# POWER_reset.net
KiCad netlist of a schematic drawn in EAGLE
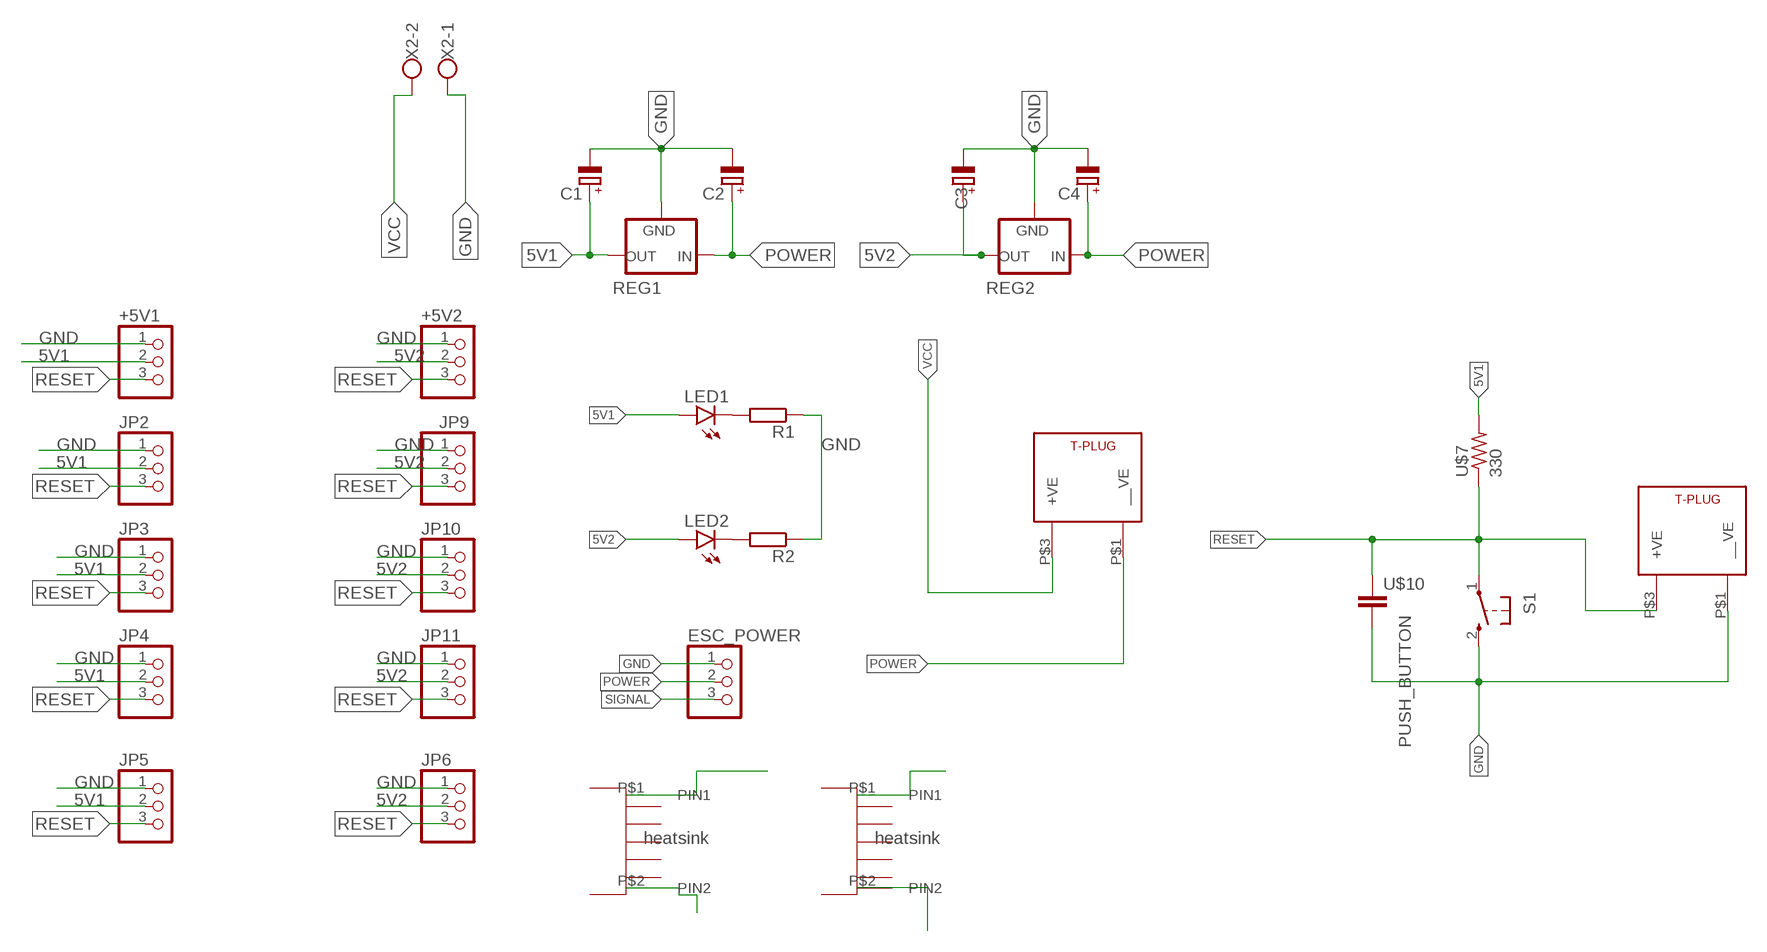
[diagram p0: schematic, sheet 1]

(export (version "E")
  (design (tool "Eeschema 10.0.6"))
  (components
    (comp (ref "+5V1")
      (value "PINHD-3_DATA")
      (footprint "eagle-import:1X03_DATA")
      (libsource (lib "eagle-import") (part "PINHD-3_DATA"))
    )
    (comp (ref "+5V2")
      (value "PINHD-3_DATA")
      (footprint "eagle-import:1X03_DATA")
      (libsource (lib "eagle-import") (part "PINHD-3_DATA"))
    )
    (comp (ref "C1")
      (value "CAP_POL")
      (footprint "eagle-import:E3,5-8")
      (libsource (lib "eagle-import") (part "CAP_POL"))
    )
    (comp (ref "C2")
      (value "CAP_POL")
      (footprint "eagle-import:E3,5-8")
      (libsource (lib "eagle-import") (part "CAP_POL"))
    )
    (comp (ref "C3")
      (value "CAP_POL")
      (footprint "eagle-import:E3,5-8")
      (libsource (lib "eagle-import") (part "CAP_POL"))
    )
    (comp (ref "C4")
      (value "CAP_POL")
      (footprint "eagle-import:E3,5-8")
      (libsource (lib "eagle-import") (part "CAP_POL"))
    )
    (comp (ref "ESC_POWER")
      (value "PINHD-3_DATA")
      (footprint "eagle-import:1X03_DATA")
      (libsource (lib "eagle-import") (part "PINHD-3_DATA"))
    )
    (comp (ref "JP2")
      (value "PINHD-3_DATA")
      (footprint "eagle-import:1X03_DATA")
      (libsource (lib "eagle-import") (part "PINHD-3_DATA"))
    )
    (comp (ref "JP3")
      (value "PINHD-3_DATA")
      (footprint "eagle-import:1X03_DATA")
      (libsource (lib "eagle-import") (part "PINHD-3_DATA"))
    )
    (comp (ref "JP4")
      (value "PINHD-3_DATA")
      (footprint "eagle-import:1X03_DATA")
      (libsource (lib "eagle-import") (part "PINHD-3_DATA"))
    )
    (comp (ref "JP5")
      (value "PINHD-3_DATA")
      (footprint "eagle-import:1X03_DATA")
      (libsource (lib "eagle-import") (part "PINHD-3_DATA"))
    )
    (comp (ref "JP6")
      (value "PINHD-3_DATA")
      (footprint "eagle-import:1X03_DATA")
      (libsource (lib "eagle-import") (part "PINHD-3_DATA"))
    )
    (comp (ref "JP9")
      (value "PINHD-3_DATA")
      (footprint "eagle-import:1X03_DATA")
      (libsource (lib "eagle-import") (part "PINHD-3_DATA"))
    )
    (comp (ref "JP10")
      (value "PINHD-3_DATA")
      (footprint "eagle-import:1X03_DATA")
      (libsource (lib "eagle-import") (part "PINHD-3_DATA"))
    )
    (comp (ref "JP11")
      (value "PINHD-3_DATA")
      (footprint "eagle-import:1X03_DATA")
      (libsource (lib "eagle-import") (part "PINHD-3_DATA"))
    )
    (comp (ref "LED1")
      (value "LED5MM")
      (footprint "eagle-import:LED5MM")
      (libsource (lib "eagle-import") (part "LED5MM"))
    )
    (comp (ref "LED2")
      (value "LED5MM")
      (footprint "eagle-import:LED5MM")
      (libsource (lib "eagle-import") (part "LED5MM"))
    )
    (comp (ref "R1")
      (value "R-EU_0204/7")
      (footprint "eagle-import:0204_7")
      (libsource (lib "eagle-import") (part "R-EU_0204/7"))
    )
    (comp (ref "R2")
      (value "R-EU_0204/7")
      (footprint "eagle-import:0204_7")
      (libsource (lib "eagle-import") (part "R-EU_0204/7"))
    )
    (comp (ref "REG1")
      (value "78XXS")
      (footprint "eagle-import:78XXS")
      (libsource (lib "eagle-import") (part "78XXS"))
    )
    (comp (ref "REG2")
      (value "78XXS")
      (footprint "eagle-import:78XXS")
      (libsource (lib "eagle-import") (part "78XXS"))
    )
    (comp (ref "S1")
      (value "PUSH_BUTTON")
      (footprint "eagle-import:B3F-10XX")
      (libsource (lib "eagle-import") (part "PUSH_BUTTON"))
    )
    (comp (ref "U$1")
      (value "HEAT-SINK")
      (footprint "eagle-import:HEAT_SINK")
      (libsource (lib "eagle-import") (part "HEAT-SINK"))
    )
    (comp (ref "U$2")
      (value "HEAT-SINK")
      (footprint "eagle-import:HEAT_SINK")
      (libsource (lib "eagle-import") (part "HEAT-SINK"))
    )
    (comp (ref "U$3")
      (value "T_CONNECTOR")
      (footprint "eagle-import:T-PLUG")
      (libsource (lib "eagle-import") (part "T_CONNECTOR"))
    )
    (comp (ref "U$4")
      (value "T_CONNECTOR")
      (footprint "eagle-import:T-PLUG")
      (libsource (lib "eagle-import") (part "T_CONNECTOR"))
    )
    (comp (ref "U$7")
      (value "330")
      (footprint "eagle-import:0204_7")
      (libsource (lib "eagle-import") (part "RES-7"))
    )
    (comp (ref "U$10")
      (value "CAPACITOR")
      (footprint "eagle-import:C025-025X050")
      (libsource (lib "eagle-import") (part "CAPACITOR"))
    )
    (comp (ref "X2")
      (value "ROSTA.POWER")
      (footprint "eagle-import:W239-302")
      (libsource (lib "eagle-import") (part "ROSTA.POWER"))
    )
  )
  (nets
    (net (code "1") (name "5V1") (class "Default")
      (node (ref "+5V1") (pin "2") (pinfunction "2_2") (pintype "passive"))
      (node (ref "C1") (pin "+") (pinfunction "+_+") (pintype "passive"))
      (node (ref "JP2") (pin "2") (pinfunction "2_2") (pintype "passive"))
      (node (ref "JP3") (pin "2") (pinfunction "2_2") (pintype "passive"))
      (node (ref "JP4") (pin "2") (pinfunction "2_2") (pintype "passive"))
      (node (ref "JP5") (pin "2") (pinfunction "2_2") (pintype "passive"))
      (node (ref "LED1") (pin "A") (pinfunction "A_A") (pintype "passive"))
      (node (ref "REG1") (pin "OUT") (pinfunction "OUT_OUT") (pintype "passive"))
      (node (ref "U$7") (pin "2") (pinfunction "2_2") (pintype "passive"))
    )
    (net (code "2") (name "5V2") (class "Default")
      (node (ref "+5V2") (pin "2") (pinfunction "2_2") (pintype "passive"))
      (node (ref "C3") (pin "+") (pinfunction "+_+") (pintype "passive"))
      (node (ref "JP10") (pin "2") (pinfunction "2_2") (pintype "passive"))
      (node (ref "JP11") (pin "2") (pinfunction "2_2") (pintype "passive"))
      (node (ref "JP6") (pin "2") (pinfunction "2_2") (pintype "passive"))
      (node (ref "JP9") (pin "2") (pinfunction "2_2") (pintype "passive"))
      (node (ref "LED2") (pin "A") (pinfunction "A_A") (pintype "passive"))
      (node (ref "REG2") (pin "OUT") (pinfunction "OUT_OUT") (pintype "passive"))
    )
    (net (code "3") (name "GND") (class "Default")
      (node (ref "+5V1") (pin "1") (pinfunction "1_1") (pintype "passive"))
      (node (ref "+5V2") (pin "1") (pinfunction "1_1") (pintype "passive"))
      (node (ref "C1") (pin "-") (pinfunction "-_-") (pintype "passive"))
      (node (ref "C2") (pin "-") (pinfunction "-_-") (pintype "passive"))
      (node (ref "C3") (pin "-") (pinfunction "-_-") (pintype "passive"))
      (node (ref "C4") (pin "-") (pinfunction "-_-") (pintype "passive"))
      (node (ref "ESC_POWER") (pin "1") (pinfunction "1_1") (pintype "passive"))
      (node (ref "JP10") (pin "1") (pinfunction "1_1") (pintype "passive"))
      (node (ref "JP11") (pin "1") (pinfunction "1_1") (pintype "passive"))
      (node (ref "JP2") (pin "1") (pinfunction "1_1") (pintype "passive"))
      (node (ref "JP3") (pin "1") (pinfunction "1_1") (pintype "passive"))
      (node (ref "JP4") (pin "1") (pinfunction "1_1") (pintype "passive"))
      (node (ref "JP5") (pin "1") (pinfunction "1_1") (pintype "passive"))
      (node (ref "JP6") (pin "1") (pinfunction "1_1") (pintype "passive"))
      (node (ref "JP9") (pin "1") (pinfunction "1_1") (pintype "passive"))
      (node (ref "R1") (pin "1") (pinfunction "1_1") (pintype "passive"))
      (node (ref "R2") (pin "1") (pinfunction "1_1") (pintype "passive"))
      (node (ref "REG1") (pin "GND") (pinfunction "GND_GND") (pintype "input"))
      (node (ref "REG2") (pin "GND") (pinfunction "GND_GND") (pintype "input"))
      (node (ref "S1") (pin "2") (pinfunction "S_2") (pintype "passive"))
      (node (ref "U$10") (pin "2") (pinfunction "2_2") (pintype "passive"))
      (node (ref "U$3") (pin "P$1") (pinfunction "__VE_P$1") (pintype "bidirectional"))
      (node (ref "X2") (pin "1") (pinfunction "KL_1") (pintype "passive"))
    )
    (net (code "4") (name "Net-(LED1-C)") (class "Default")
      (node (ref "LED1") (pin "K") (pinfunction "C_K") (pintype "passive"))
      (node (ref "R1") (pin "2") (pinfunction "2_2") (pintype "passive"))
    )
    (net (code "5") (name "Net-(LED2-C)") (class "Default")
      (node (ref "LED2") (pin "K") (pinfunction "C_K") (pintype "passive"))
      (node (ref "R2") (pin "2") (pinfunction "2_2") (pintype "passive"))
    )
    (net (code "6") (name "POWER") (class "Default")
      (node (ref "C2") (pin "+") (pinfunction "+_+") (pintype "passive"))
      (node (ref "C4") (pin "+") (pinfunction "+_+") (pintype "passive"))
      (node (ref "ESC_POWER") (pin "2") (pinfunction "2_2") (pintype "passive"))
      (node (ref "REG1") (pin "IN") (pinfunction "IN_IN") (pintype "input"))
      (node (ref "REG2") (pin "IN") (pinfunction "IN_IN") (pintype "input"))
      (node (ref "U$4") (pin "P$1") (pinfunction "__VE_P$1") (pintype "bidirectional"))
    )
    (net (code "7") (name "RESET") (class "Default")
      (node (ref "+5V1") (pin "3") (pinfunction "3_3") (pintype "passive"))
      (node (ref "+5V2") (pin "3") (pinfunction "3_3") (pintype "passive"))
      (node (ref "JP10") (pin "3") (pinfunction "3_3") (pintype "passive"))
      (node (ref "JP11") (pin "3") (pinfunction "3_3") (pintype "passive"))
      (node (ref "JP2") (pin "3") (pinfunction "3_3") (pintype "passive"))
      (node (ref "JP3") (pin "3") (pinfunction "3_3") (pintype "passive"))
      (node (ref "JP4") (pin "3") (pinfunction "3_3") (pintype "passive"))
      (node (ref "JP5") (pin "3") (pinfunction "3_3") (pintype "passive"))
      (node (ref "JP6") (pin "3") (pinfunction "3_3") (pintype "passive"))
      (node (ref "JP9") (pin "3") (pinfunction "3_3") (pintype "passive"))
      (node (ref "S1") (pin "1") (pinfunction "P_1") (pintype "passive"))
      (node (ref "U$10") (pin "1") (pinfunction "1_1") (pintype "passive"))
      (node (ref "U$3") (pin "P$3") (pinfunction "+VE_P$3") (pintype "bidirectional"))
      (node (ref "U$7") (pin "1") (pinfunction "1_1") (pintype "passive"))
    )
    (net (code "8") (name "SIGNAL") (class "Default")
      (node (ref "ESC_POWER") (pin "3") (pinfunction "3_3") (pintype "passive"))
    )
    (net (code "9") (name "VCC") (class "Default")
      (node (ref "U$4") (pin "P$3") (pinfunction "+VE_P$3") (pintype "bidirectional"))
      (node (ref "X2") (pin "2") (pinfunction "KL_2") (pintype "passive"))
    )
    (net (code "10") (name "unconnected-(U$1-PIN1-PadP$1)") (class "Default")
      (node (ref "U$1") (pin "P$1") (pinfunction "PIN1_P$1") (pintype "bidirectional"))
    )
    (net (code "11") (name "unconnected-(U$1-PIN2-PadP$2)") (class "Default")
      (node (ref "U$1") (pin "P$2") (pinfunction "PIN2_P$2") (pintype "bidirectional"))
    )
    (net (code "12") (name "unconnected-(U$2-PIN1-PadP$1)") (class "Default")
      (node (ref "U$2") (pin "P$1") (pinfunction "PIN1_P$1") (pintype "bidirectional"))
    )
    (net (code "13") (name "unconnected-(U$2-PIN2-PadP$2)") (class "Default")
      (node (ref "U$2") (pin "P$2") (pinfunction "PIN2_P$2") (pintype "bidirectional"))
    )
  )
)
